# ROL2-C1-P01.net
KiCad netlist of a schematic drawn in Altium Designer
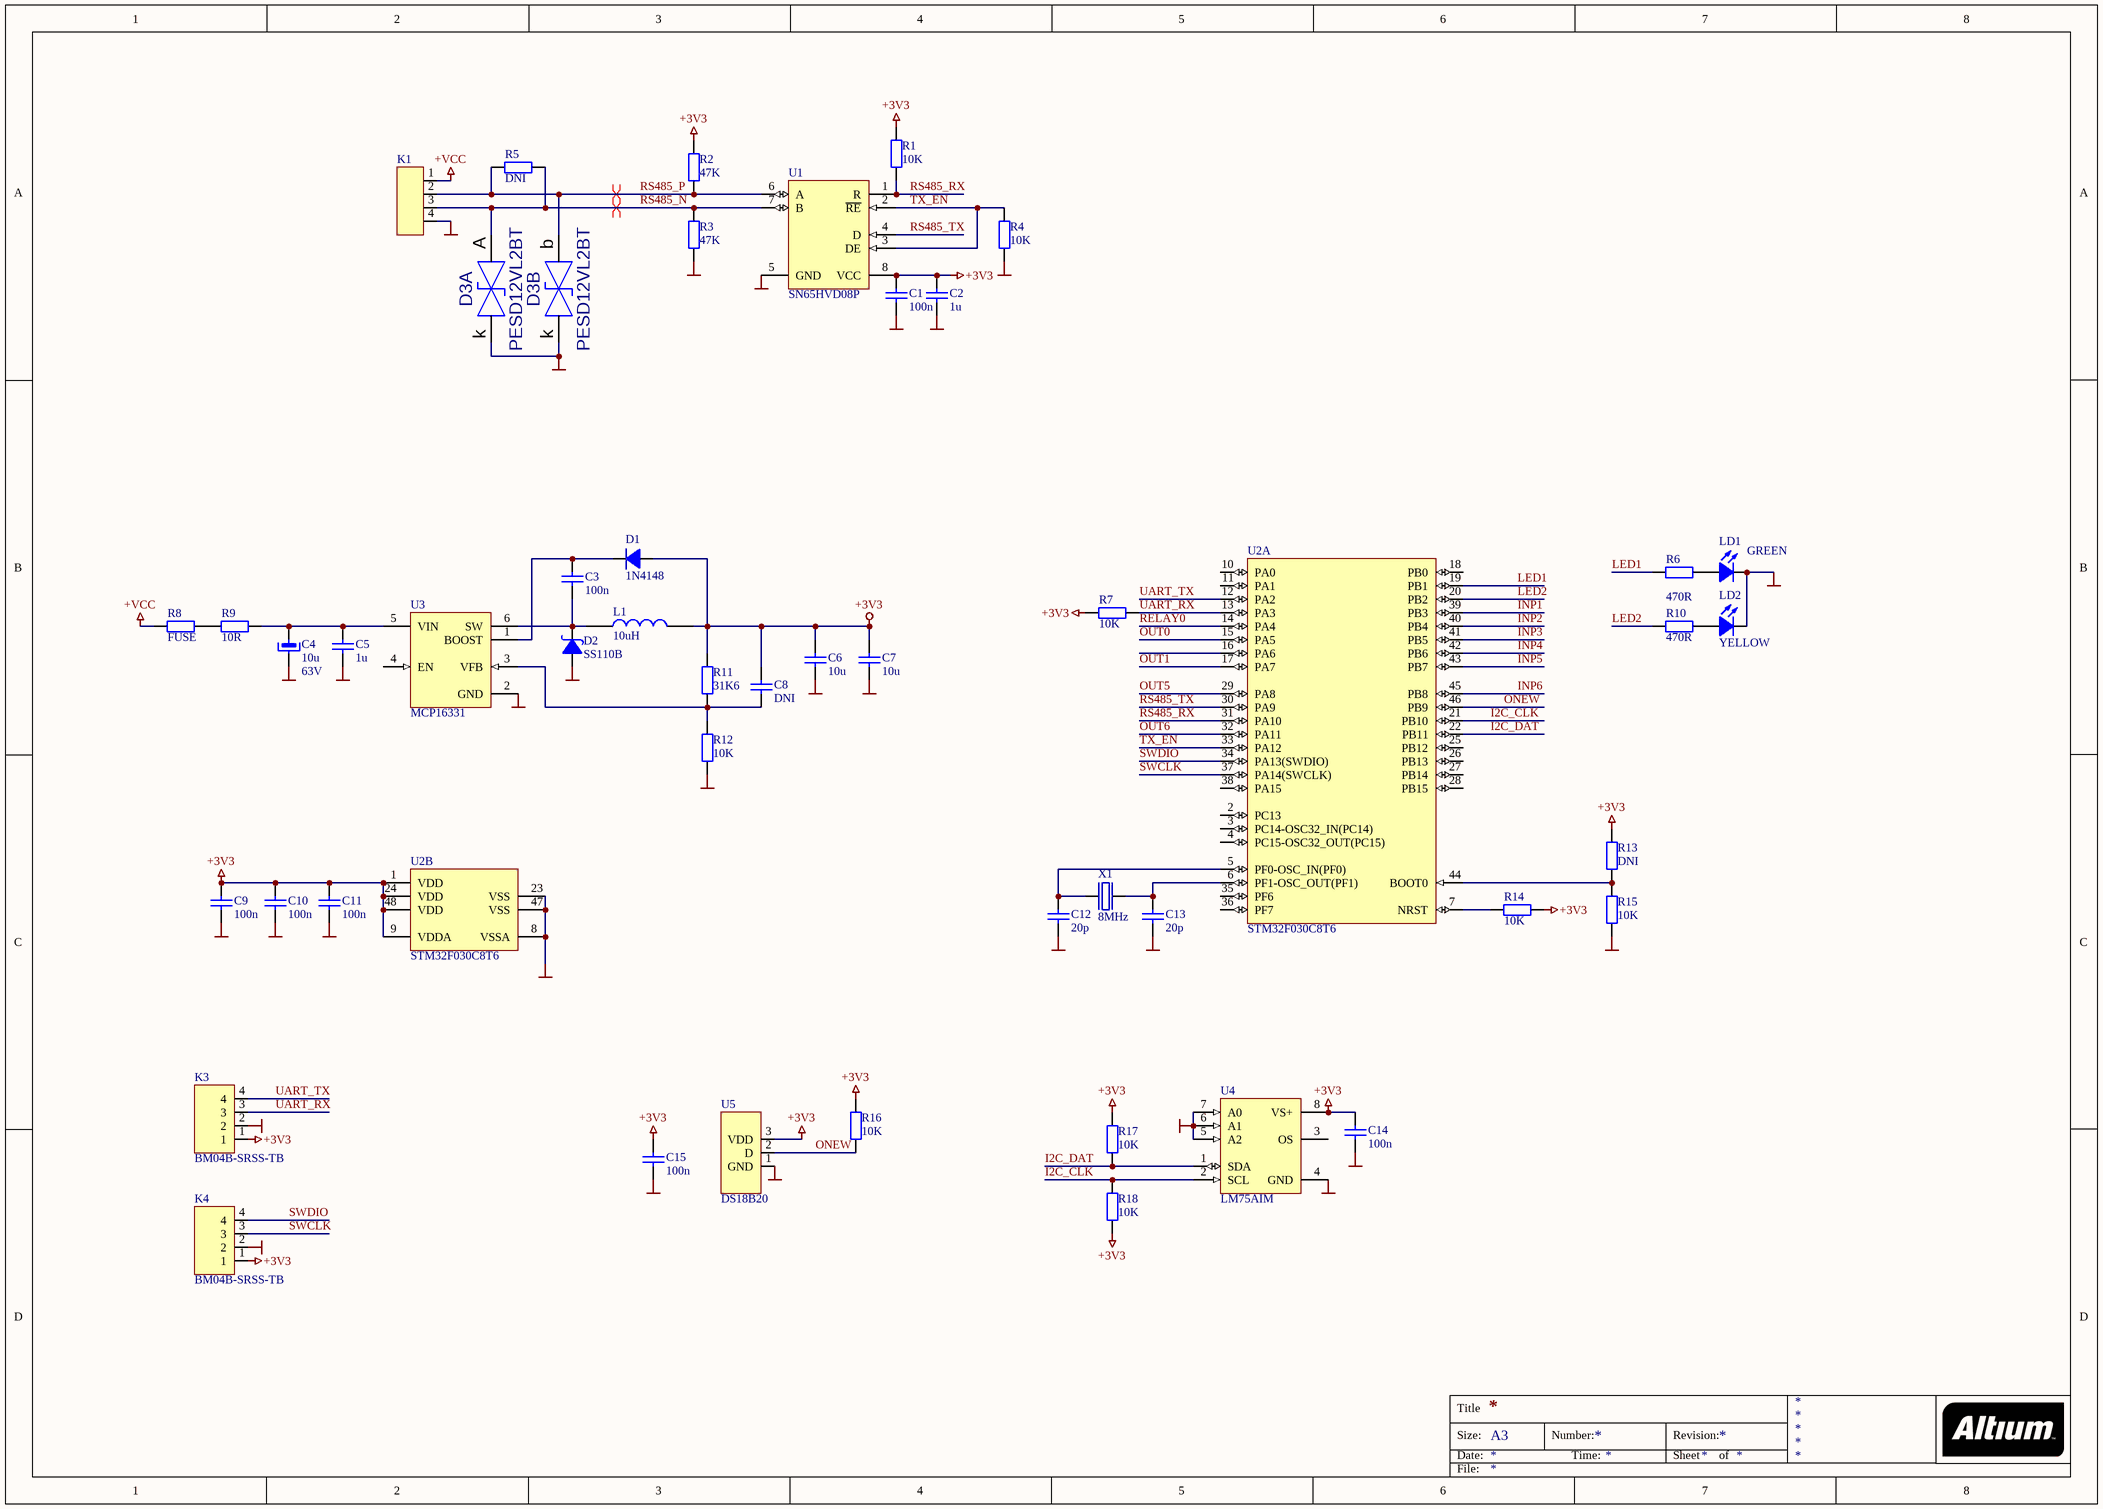
[diagram p0: ROL2-C1-P01.SchDoc]

(export (version "E")
  (design (tool "Eeschema 10.0.6"))
  (components
    (comp (ref "C1")
      (value "100n")
      (footprint "Passive:CC0805-1")
      (description "Capacitor chip ceramic 0805")
      (libsource (lib "CapChipCer") (part "CAPCC0805_1U50VX7R"))
    )
    (comp (ref "C2")
      (value "1u")
      (footprint "Passive:CC0805-1")
      (description "Capacitor chip ceramic 0805")
      (libsource (lib "CapChipCer") (part "CAPCC0805_1U50VX7R"))
    )
    (comp (ref "C3")
      (value "100n")
      (footprint "Passive:CC0805-1")
      (description "Capacitor chip ceramic 0805")
      (libsource (lib "CapChipCer") (part "CAPCC0805_1U50VX7R"))
    )
    (comp (ref "C4")
      (value "10u")
      (footprint "CAPPS-D6.3X7.7")
      (description "Capacitor electrolitic SMD 6.3X6.3X7.7MM low ESR")
      (fields (field (name "COMMENT2") "63V"))
      (libsource (lib "CapElectTht") (part "CAPPS100U25VFP"))
    )
    (comp (ref "C5")
      (value "1u")
      (footprint "Passive:CC1210-1")
      (description "Capacitor chip ceramic 1210")
      (libsource (lib "CapChipCer") (part "CAPCC1210_1U100VX7R"))
    )
    (comp (ref "C6")
      (value "10u")
      (footprint "CC0805-1")
      (description "Capacitor chip ceramic 0805")
      (libsource (lib "CapChipCer") (part "CAPCC0805_10U16VX5R"))
    )
    (comp (ref "C7")
      (value "10u")
      (footprint "CC0805-1")
      (description "Capacitor chip ceramic 0805")
      (libsource (lib "CapChipCer") (part "CAPCC0805_10U16VX5R"))
    )
    (comp (ref "C8")
      (value "DNI")
      (footprint "Passive:CC0805-1")
      (description "Capacitor chip ceramic 0805")
      (libsource (lib "CapChipCer") (part "CAPCC0805_1U50VX7R"))
    )
    (comp (ref "C9")
      (value "100n")
      (footprint "CC0805-1")
      (description "Capacitor chip ceramic 0805")
      (libsource (lib "CapChipCer") (part "CAPCC0805_100N50VX7R"))
    )
    (comp (ref "C10")
      (value "100n")
      (footprint "CC0805-1")
      (description "Capacitor chip ceramic 0805")
      (libsource (lib "CapChipCer") (part "CAPCC0805_100N50VX7R"))
    )
    (comp (ref "C11")
      (value "100n")
      (footprint "CC0805-1")
      (description "Capacitor chip ceramic 0805")
      (libsource (lib "CapChipCer") (part "CAPCC0805_100N50VX7R"))
    )
    (comp (ref "C12")
      (value "20p")
      (footprint "CC0805-1")
      (description "Capacitor chip ceramic 0805")
      (libsource (lib "CapChipCer") (part "CAPCC0805_100N50VX7R"))
    )
    (comp (ref "C13")
      (value "20p")
      (footprint "CC0805-1")
      (description "Capacitor chip ceramic 0805")
      (libsource (lib "CapChipCer") (part "CAPCC0805_100N50VX7R"))
    )
    (comp (ref "C14")
      (value "100n")
      (footprint "CC0805-1")
      (description "Capacitor chip ceramic 0805")
      (libsource (lib "CapChipCer") (part "CAPCC0805_100N50VX7R"))
    )
    (comp (ref "C15")
      (value "100n")
      (footprint "CC0805-1")
      (description "Capacitor chip ceramic 0805")
      (libsource (lib "CapChipCer") (part "CAPCC0805_100N50VX7R"))
    )
    (comp (ref "D1")
      (value "1N4148")
      (footprint "Active:SOD323")
      (description "Small Signal Diode")
      (fields (field (name "MANUFACTURER") "Vishay"))
      (libsource (lib "Discrete") (part "D-1N4148WS"))
    )
    (comp (ref "D2")
      (value "SS110B")
      (footprint "Passive:DO-214AC")
      (description "Schottky Diode")
      (fields (field (name "MANUFACTURER") "multicomp"))
      (libsource (lib "Discrete") (part "CD214A-B240LF-0.3V@1A"))
    )
    (comp (ref "D3")
      (value "PESD12VL2BT")
      (footprint "SOT-23_NUP2105L(Primary)")
      (description "Diode")
      (libsource (lib "fractal_lib") (part "NUP2105L"))
    )
    (comp (ref "K1")
      (value "Terminal Block Connector, 3.81mm, Right Angle")
      (footprint "CONN_3.81_4")
      (description "Terminal Block Connector, 3.81mm, 4pin")
      (libsource (lib "fractal_lib") (part "CONN_TB_3.81_4PIN"))
    )
    (comp (ref "K3")
      (value "BM04B-SRSS-TB")
      (footprint "JST-SH-4pin")
      (description "JST connector 4pin vertical")
      (libsource (lib "fractal_lib") (part "JST-SH-BM04B-SRSS-TB"))
    )
    (comp (ref "K4")
      (value "BM04B-SRSS-TB")
      (footprint "JST-SH-4pin")
      (description "JST connector 4pin vertical")
      (libsource (lib "fractal_lib") (part "JST-SH-BM04B-SRSS-TB"))
    )
    (comp (ref "L1")
      (value "10uH")
      (footprint "IND-LQH32CN4R7M33l")
      (description "Chip Inductor 4 x 4 mm")
      (fields (field (name "MANUFACTURER") "Murata"))
      (libsource (lib "Induct") (part "LQH44PN100MP0L"))
    )
    (comp (ref "LD1")
      (value "GREEN")
      (footprint "Active:LEDGREENC190")
      (description "LED green HSMG vertical")
      (fields (field (name "MANUFACTURER") "Avago"))
      (libsource (lib "Discrete") (part "LED-GREEN0603V"))
    )
    (comp (ref "LD2")
      (value "YELLOW")
      (footprint "Active:LEDYELLOWC190")
      (description "LED yellow HSMY vertical")
      (fields (field (name "MANUFACTURER") "Avago"))
      (libsource (lib "Discrete") (part "LED-YELLOW0603V"))
    )
    (comp (ref "R1")
      (value "10K")
      (footprint "RC0805-1")
      (description "Chip Resistor 0805")
      (libsource (lib "") (part "RES0805_1"))
    )
    (comp (ref "R2")
      (value "47K")
      (footprint "RC0805-1")
      (description "Chip Resistor 0805")
      (libsource (lib "Resistors") (part "RES0805"))
    )
    (comp (ref "R3")
      (value "47K")
      (footprint "RC0805-1")
      (description "Chip Resistor 0805")
      (libsource (lib "Resistors") (part "RES0805"))
    )
    (comp (ref "R4")
      (value "10K")
      (footprint "RC0805-1")
      (description "Chip Resistor 0805")
      (libsource (lib "") (part "RES0805_1"))
    )
    (comp (ref "R5")
      (value "DNI")
      (footprint "RC0805-1")
      (description "Chip Resistor 0805")
      (libsource (lib "") (part "RES0805_1"))
    )
    (comp (ref "R6")
      (value "470R")
      (footprint "RC0805-1")
      (description "Chip Resistor 0805")
      (libsource (lib "") (part "RES0805_1"))
    )
    (comp (ref "R7")
      (value "10K")
      (footprint "RC0805-1")
      (description "Chip Resistor 0805")
      (libsource (lib "") (part "RES0805_1"))
    )
    (comp (ref "R8")
      (value "FUSE")
      (footprint "RC1206-1")
      (description "Chip Resistor 1206")
      (libsource (lib "Resistors") (part "RES1206"))
    )
    (comp (ref "R9")
      (value "10R")
      (footprint "RC0805-1")
      (description "Chip Resistor 0805")
      (libsource (lib "") (part "RES0805_3"))
    )
    (comp (ref "R10")
      (value "470R")
      (footprint "RC0805-1")
      (description "Chip Resistor 0805")
      (libsource (lib "") (part "RES0805_1"))
    )
    (comp (ref "R11")
      (value "31K6")
      (footprint "RC0805-1")
      (description "Chip Resistor 0805")
      (libsource (lib "Resistors") (part "RES0805"))
    )
    (comp (ref "R12")
      (value "10K")
      (footprint "RC0805-1")
      (description "Chip Resistor 0805")
      (libsource (lib "Resistors") (part "RES0805"))
    )
    (comp (ref "R13")
      (value "DNI")
      (footprint "RC0805-1")
      (description "Chip Resistor 0805")
      (libsource (lib "Resistors") (part "RES0805"))
    )
    (comp (ref "R14")
      (value "10K")
      (footprint "RC0805-1")
      (description "Chip Resistor 0805")
      (libsource (lib "") (part "RES0805_3"))
    )
    (comp (ref "R15")
      (value "10K")
      (footprint "RC0805-1")
      (description "Chip Resistor 0805")
      (libsource (lib "") (part "RES0805_2"))
    )
    (comp (ref "R16")
      (value "10K")
      (footprint "RC0805-1")
      (description "Chip Resistor 0805")
      (libsource (lib "") (part "RES0805_2"))
    )
    (comp (ref "R17")
      (value "10K")
      (footprint "RC0805-1")
      (description "Chip Resistor 0805")
      (libsource (lib "") (part "RES0805_2"))
    )
    (comp (ref "R18")
      (value "10K")
      (footprint "RC0805-1")
      (description "Chip Resistor 0805")
      (libsource (lib "Resistors") (part "RES0805"))
    )
    (comp (ref "U1")
      (value "SN65HVD08P")
      (footprint "M08A_M")
      (description "3.3 / 5 V RS-485 Transceiver, 10 Mbps, Half Duplex, -40 to 85 degC, 8-pin PDIP (P), Pb-Free (RoHS)")
      (fields (field (name "MANUFACTURER") "Texas Instruments"))
      (libsource (lib "fractal_lib") (part "SN65HVD08P"))
    )
    (comp (ref "U2")
      (value "STM32F030C8T6")
      (footprint "STM-LQFP48_N")
      (libsource (lib "fractal_lib") (part "STM32F030C8T6"))
    )
    (comp (ref "U3")
      (value "MCP16331")
      (footprint "MCHP-SOT-23-CH6_N")
      (fields (field (name "MANUFACTURER") "Microchip") (field (name "PARTNUMBER") "MCP16301T-E/CH"))
      (libsource (lib "fractal_lib") (part "MCP16301T-E/CH"))
    )
    (comp (ref "U4")
      (value "LM75AIM")
      (footprint "M08A_N")
      (description "Digital Temperature Sensor and Thermal Watchdog with Two-Wire Interface, 8-pin Narrow SOIC")
      (fields (field (name "MANUFACTURER") "National Semiconductor"))
      (libsource (lib "fractal_lib") (part "LM75AIM"))
    )
    (comp (ref "U5")
      (value "DS18B20")
      (footprint "TO92")
      (description "digital temperature sensor")
      (libsource (lib "fractal_lib") (part "DS18B20"))
    )
    (comp (ref "X1")
      (value "8MHz")
      (footprint "OSCCC150X320X9-2N_big")
      (description "SMD Crystal 8MHz")
      (libsource (lib "fractal_lib") (part "XTAL-SMD_8MHz"))
    )
  )
  (nets
    (net (code "1") (name "+3V3") (class "Default")
      (node (ref "C1") (pin "2") (pinfunction "2_2") (pintype "passive"))
      (node (ref "C10") (pin "2") (pinfunction "2_2") (pintype "passive"))
      (node (ref "C11") (pin "2") (pinfunction "2_2") (pintype "passive"))
      (node (ref "C14") (pin "2") (pinfunction "2_2") (pintype "passive"))
      (node (ref "C15") (pin "2") (pinfunction "2_2") (pintype "passive"))
      (node (ref "C2") (pin "2") (pinfunction "2_2") (pintype "passive"))
      (node (ref "C6") (pin "2") (pinfunction "2_2") (pintype "passive"))
      (node (ref "C7") (pin "2") (pinfunction "2_2") (pintype "passive"))
      (node (ref "C8") (pin "2") (pinfunction "2_2") (pintype "passive"))
      (node (ref "C9") (pin "2") (pinfunction "2_2") (pintype "passive"))
      (node (ref "D1") (pin "2") (pinfunction "A_2") (pintype "passive"))
      (node (ref "K3") (pin "1") (pinfunction "1_1") (pintype "passive"))
      (node (ref "K4") (pin "1") (pinfunction "1_1") (pintype "passive"))
      (node (ref "L1") (pin "2") (pinfunction "2_2") (pintype "passive"))
      (node (ref "R1") (pin "2") (pinfunction "2_2") (pintype "passive"))
      (node (ref "R11") (pin "2") (pinfunction "2_2") (pintype "passive"))
      (node (ref "R13") (pin "2") (pinfunction "2_2") (pintype "passive"))
      (node (ref "R14") (pin "1") (pinfunction "1_1") (pintype "passive"))
      (node (ref "R16") (pin "1") (pinfunction "1_1") (pintype "passive"))
      (node (ref "R17") (pin "1") (pinfunction "1_1") (pintype "passive"))
      (node (ref "R18") (pin "1") (pinfunction "1_1") (pintype "passive"))
      (node (ref "R2") (pin "2") (pinfunction "2_2") (pintype "passive"))
      (node (ref "R7") (pin "1") (pinfunction "1_1") (pintype "passive"))
      (node (ref "U1") (pin "8") (pinfunction "VCC_8") (pintype "power_in"))
      (node (ref "U2") (pin "1") (pinfunction "VDD_1") (pintype "power_in"))
      (node (ref "U2") (pin "24") (pinfunction "VDD_24") (pintype "power_in"))
      (node (ref "U2") (pin "48") (pinfunction "VDD_48") (pintype "power_in"))
      (node (ref "U2") (pin "9") (pinfunction "VDDA_9") (pintype "power_in"))
      (node (ref "U4") (pin "8") (pinfunction "VS+_8") (pintype "power_in"))
      (node (ref "U5") (pin "3") (pinfunction "VDD_3") (pintype "passive"))
    )
    (net (code "2") (name "+VCC") (class "Default")
      (node (ref "K1") (pin "1") (pinfunction "A_1") (pintype "passive"))
      (node (ref "R8") (pin "1") (pinfunction "1_1") (pintype "passive"))
    )
    (net (code "3") (name "/I2C_CLK") (class "Default")
      (node (ref "R18") (pin "2") (pinfunction "2_2") (pintype "passive"))
      (node (ref "U2") (pin "21") (pinfunction "PB10_21") (pintype "bidirectional"))
      (node (ref "U4") (pin "2") (pinfunction "SCL_2") (pintype "input"))
    )
    (net (code "4") (name "/I2C_DAT") (class "Default")
      (node (ref "R17") (pin "2") (pinfunction "2_2") (pintype "passive"))
      (node (ref "U2") (pin "22") (pinfunction "PB11_22") (pintype "bidirectional"))
      (node (ref "U4") (pin "1") (pinfunction "SDA_1") (pintype "bidirectional"))
    )
    (net (code "5") (name "/INP1") (class "Default")
      (node (ref "U2") (pin "39") (pinfunction "PB3_39") (pintype "bidirectional"))
    )
    (net (code "6") (name "/INP2") (class "Default")
      (node (ref "U2") (pin "40") (pinfunction "PB4_40") (pintype "bidirectional"))
    )
    (net (code "7") (name "/INP3") (class "Default")
      (node (ref "U2") (pin "41") (pinfunction "PB5_41") (pintype "bidirectional"))
    )
    (net (code "8") (name "/INP4") (class "Default")
      (node (ref "U2") (pin "42") (pinfunction "PB6_42") (pintype "bidirectional"))
    )
    (net (code "9") (name "/INP5") (class "Default")
      (node (ref "U2") (pin "43") (pinfunction "PB7_43") (pintype "bidirectional"))
    )
    (net (code "10") (name "/INP6") (class "Default")
      (node (ref "U2") (pin "45") (pinfunction "PB8_45") (pintype "bidirectional"))
    )
    (net (code "11") (name "/LED1") (class "Default")
      (node (ref "R6") (pin "1") (pinfunction "1_1") (pintype "passive"))
      (node (ref "U2") (pin "19") (pinfunction "PB1_19") (pintype "bidirectional"))
    )
    (net (code "12") (name "/LED2") (class "Default")
      (node (ref "R10") (pin "1") (pinfunction "1_1") (pintype "passive"))
      (node (ref "U2") (pin "20") (pinfunction "PB2_20") (pintype "bidirectional"))
    )
    (net (code "13") (name "/ONEW") (class "Default")
      (node (ref "R16") (pin "2") (pinfunction "2_2") (pintype "passive"))
      (node (ref "U2") (pin "46") (pinfunction "PB9_46") (pintype "bidirectional"))
      (node (ref "U5") (pin "2") (pinfunction "D_2") (pintype "passive"))
    )
    (net (code "14") (name "/OUT0") (class "Default")
      (node (ref "U2") (pin "15") (pinfunction "PA5_15") (pintype "bidirectional"))
    )
    (net (code "15") (name "/OUT1") (class "Default")
      (node (ref "U2") (pin "17") (pinfunction "PA7_17") (pintype "bidirectional"))
    )
    (net (code "16") (name "/OUT5") (class "Default")
      (node (ref "U2") (pin "29") (pinfunction "PA8_29") (pintype "bidirectional"))
    )
    (net (code "17") (name "/OUT6") (class "Default")
      (node (ref "U2") (pin "32") (pinfunction "PA11_32") (pintype "bidirectional"))
    )
    (net (code "18") (name "/RELAY0") (class "Default")
      (node (ref "U2") (pin "14") (pinfunction "PA4_14") (pintype "bidirectional"))
    )
    (net (code "19") (name "/RS485_N") (class "Default")
      (node (ref "D3") (pin "A") (pinfunction "A_A") (pintype "passive"))
      (node (ref "K1") (pin "3") (pinfunction "A_3") (pintype "passive"))
      (node (ref "R3") (pin "2") (pinfunction "2_2") (pintype "passive"))
      (node (ref "R5") (pin "2") (pinfunction "2_2") (pintype "passive"))
      (node (ref "U1") (pin "7") (pinfunction "B_7") (pintype "bidirectional"))
    )
    (net (code "20") (name "/RS485_P") (class "Default")
      (node (ref "D3") (pin "b") (pinfunction "A_b") (pintype "passive"))
      (node (ref "K1") (pin "2") (pinfunction "K_2") (pintype "passive"))
      (node (ref "R2") (pin "1") (pinfunction "1_1") (pintype "passive"))
      (node (ref "R5") (pin "1") (pinfunction "1_1") (pintype "passive"))
      (node (ref "U1") (pin "6") (pinfunction "A_6") (pintype "bidirectional"))
    )
    (net (code "21") (name "/RS485_RX") (class "Default")
      (node (ref "R1") (pin "1") (pinfunction "1_1") (pintype "passive"))
      (node (ref "U1") (pin "1") (pinfunction "R_1") (pintype "tri_state"))
      (node (ref "U2") (pin "31") (pinfunction "PA10_31") (pintype "bidirectional"))
    )
    (net (code "22") (name "/RS485_TX") (class "Default")
      (node (ref "U1") (pin "4") (pinfunction "D_4") (pintype "input"))
      (node (ref "U2") (pin "30") (pinfunction "PA9_30") (pintype "bidirectional"))
    )
    (net (code "23") (name "/SWCLK") (class "Default")
      (node (ref "K4") (pin "3") (pinfunction "3_3") (pintype "passive"))
      (node (ref "U2") (pin "37") (pinfunction "PA14(SWCLK)_37") (pintype "bidirectional"))
    )
    (net (code "24") (name "/SWDIO") (class "Default")
      (node (ref "K4") (pin "4") (pinfunction "4_4") (pintype "passive"))
      (node (ref "U2") (pin "34") (pinfunction "PA13(SWDIO)_34") (pintype "bidirectional"))
    )
    (net (code "25") (name "/TX_EN") (class "Default")
      (node (ref "R4") (pin "2") (pinfunction "2_2") (pintype "passive"))
      (node (ref "U1") (pin "2") (pinfunction "~{RE}_2") (pintype "input"))
      (node (ref "U1") (pin "3") (pinfunction "DE_3") (pintype "input"))
      (node (ref "U2") (pin "33") (pinfunction "PA12_33") (pintype "bidirectional"))
    )
    (net (code "26") (name "/UART_RX") (class "Default")
      (node (ref "K3") (pin "3") (pinfunction "3_3") (pintype "passive"))
      (node (ref "R7") (pin "2") (pinfunction "2_2") (pintype "passive"))
      (node (ref "U2") (pin "13") (pinfunction "PA3_13") (pintype "bidirectional"))
    )
    (net (code "27") (name "/UART_TX") (class "Default")
      (node (ref "K3") (pin "4") (pinfunction "4_4") (pintype "passive"))
      (node (ref "U2") (pin "12") (pinfunction "PA2_12") (pintype "bidirectional"))
    )
    (net (code "28") (name "GND") (class "Default")
      (node (ref "C1") (pin "1") (pinfunction "1_1") (pintype "passive"))
      (node (ref "C10") (pin "1") (pinfunction "1_1") (pintype "passive"))
      (node (ref "C11") (pin "1") (pinfunction "1_1") (pintype "passive"))
      (node (ref "C12") (pin "1") (pinfunction "1_1") (pintype "passive"))
      (node (ref "C13") (pin "1") (pinfunction "1_1") (pintype "passive"))
      (node (ref "C14") (pin "1") (pinfunction "1_1") (pintype "passive"))
      (node (ref "C15") (pin "1") (pinfunction "1_1") (pintype "passive"))
      (node (ref "C2") (pin "1") (pinfunction "1_1") (pintype "passive"))
      (node (ref "C4") (pin "2") (pinfunction "2_2") (pintype "passive"))
      (node (ref "C5") (pin "1") (pinfunction "1_1") (pintype "passive"))
      (node (ref "C6") (pin "1") (pinfunction "1_1") (pintype "passive"))
      (node (ref "C7") (pin "1") (pinfunction "1_1") (pintype "passive"))
      (node (ref "C9") (pin "1") (pinfunction "1_1") (pintype "passive"))
      (node (ref "D2") (pin "A") (pinfunction "A_A") (pintype "passive"))
      (node (ref "D3") (pin "k") (pinfunction "K_k") (pintype "power_in"))
      (node (ref "K1") (pin "4") (pinfunction "K_4") (pintype "passive"))
      (node (ref "K3") (pin "2") (pinfunction "2_2") (pintype "passive"))
      (node (ref "K4") (pin "2") (pinfunction "2_2") (pintype "passive"))
      (node (ref "LD1") (pin "1") (pinfunction "C_1") (pintype "passive"))
      (node (ref "LD2") (pin "1") (pinfunction "C_1") (pintype "passive"))
      (node (ref "R12") (pin "1") (pinfunction "1_1") (pintype "passive"))
      (node (ref "R15") (pin "2") (pinfunction "2_2") (pintype "passive"))
      (node (ref "R3") (pin "1") (pinfunction "1_1") (pintype "passive"))
      (node (ref "R4") (pin "1") (pinfunction "1_1") (pintype "passive"))
      (node (ref "U1") (pin "5") (pinfunction "GND_5") (pintype "power_in"))
      (node (ref "U2") (pin "23") (pinfunction "VSS_23") (pintype "power_in"))
      (node (ref "U2") (pin "47") (pinfunction "VSS_47") (pintype "power_in"))
      (node (ref "U2") (pin "8") (pinfunction "VSSA_8") (pintype "power_in"))
      (node (ref "U3") (pin "2") (pinfunction "GND_2") (pintype "power_in"))
      (node (ref "U4") (pin "4") (pinfunction "GND_4") (pintype "power_in"))
      (node (ref "U4") (pin "5") (pinfunction "A2_5") (pintype "input"))
      (node (ref "U4") (pin "6") (pinfunction "A1_6") (pintype "input"))
      (node (ref "U4") (pin "7") (pinfunction "A0_7") (pintype "input"))
      (node (ref "U5") (pin "1") (pinfunction "GND_1") (pintype "passive"))
    )
    (net (code "29") (name "Net-(D1-C)") (class "Default")
      (node (ref "C3") (pin "2") (pinfunction "2_2") (pintype "passive"))
      (node (ref "D1") (pin "1") (pinfunction "C_1") (pintype "passive"))
      (node (ref "U3") (pin "1") (pinfunction "BOOST_1") (pintype "power_in"))
    )
    (net (code "30") (name "Net-(LD1-A)") (class "Default")
      (node (ref "LD1") (pin "2") (pinfunction "A_2") (pintype "passive"))
      (node (ref "R6") (pin "2") (pinfunction "2_2") (pintype "passive"))
    )
    (net (code "31") (name "Net-(LD2-A)") (class "Default")
      (node (ref "LD2") (pin "2") (pinfunction "A_2") (pintype "passive"))
      (node (ref "R10") (pin "2") (pinfunction "2_2") (pintype "passive"))
    )
    (net (code "32") (name "Net-(R8-Pad2)") (class "Default")
      (node (ref "R8") (pin "2") (pinfunction "2_2") (pintype "passive"))
      (node (ref "R9") (pin "2") (pinfunction "2_2") (pintype "passive"))
    )
    (net (code "33") (name "Net-(U2A-BOOT0)") (class "Default")
      (node (ref "R13") (pin "1") (pinfunction "1_1") (pintype "passive"))
      (node (ref "R15") (pin "1") (pinfunction "1_1") (pintype "passive"))
      (node (ref "U2") (pin "44") (pinfunction "BOOT0_44") (pintype "input"))
    )
    (net (code "34") (name "Net-(U2A-NRST)") (class "Default")
      (node (ref "R14") (pin "2") (pinfunction "2_2") (pintype "passive"))
      (node (ref "U2") (pin "7") (pinfunction "NRST_7") (pintype "bidirectional"))
    )
    (net (code "35") (name "Net-(U2A-PF0-OSC_IN(PF0))") (class "Default")
      (node (ref "C12") (pin "2") (pinfunction "2_2") (pintype "passive"))
      (node (ref "U2") (pin "5") (pinfunction "PF0-OSC_IN(PF0)_5") (pintype "bidirectional"))
      (node (ref "X1") (pin "1") (pinfunction "OUT_1") (pintype "power_in"))
    )
    (net (code "36") (name "Net-(U2A-PF1-OSC_OUT(PF1))") (class "Default")
      (node (ref "C13") (pin "2") (pinfunction "2_2") (pintype "passive"))
      (node (ref "U2") (pin "6") (pinfunction "PF1-OSC_OUT(PF1)_6") (pintype "bidirectional"))
      (node (ref "X1") (pin "2") (pinfunction "IN_2") (pintype "passive"))
    )
    (net (code "37") (name "Net-(U3-SW)") (class "Default")
      (node (ref "C3") (pin "1") (pinfunction "1_1") (pintype "passive"))
      (node (ref "D2") (pin "K") (pinfunction "K_K") (pintype "passive"))
      (node (ref "L1") (pin "1") (pinfunction "1_1") (pintype "passive"))
      (node (ref "U3") (pin "6") (pinfunction "SW_6") (pintype "power_in"))
    )
    (net (code "38") (name "Net-(U3-VFB)") (class "Default")
      (node (ref "C8") (pin "1") (pinfunction "1_1") (pintype "passive"))
      (node (ref "R11") (pin "1") (pinfunction "1_1") (pintype "passive"))
      (node (ref "R12") (pin "2") (pinfunction "2_2") (pintype "passive"))
      (node (ref "U3") (pin "3") (pinfunction "VFB_3") (pintype "input"))
    )
    (net (code "39") (name "Net-(U3-VIN)") (class "Default")
      (node (ref "C4") (pin "1") (pinfunction "1_1") (pintype "passive"))
      (node (ref "C5") (pin "2") (pinfunction "2_2") (pintype "passive"))
      (node (ref "R9") (pin "1") (pinfunction "1_1") (pintype "passive"))
      (node (ref "U3") (pin "5") (pinfunction "VIN_5") (pintype "power_in"))
    )
    (net (code "40") (name "unconnected-(U2A-PA0-Pad10)") (class "Default")
      (node (ref "U2") (pin "10") (pinfunction "PA0_10") (pintype "bidirectional"))
    )
    (net (code "41") (name "unconnected-(U2A-PA1-Pad11)") (class "Default")
      (node (ref "U2") (pin "11") (pinfunction "PA1_11") (pintype "bidirectional"))
    )
    (net (code "42") (name "unconnected-(U2A-PA6-Pad16)") (class "Default")
      (node (ref "U2") (pin "16") (pinfunction "PA6_16") (pintype "bidirectional"))
    )
    (net (code "43") (name "unconnected-(U2A-PA15-Pad38)") (class "Default")
      (node (ref "U2") (pin "38") (pinfunction "PA15_38") (pintype "bidirectional"))
    )
    (net (code "44") (name "unconnected-(U2A-PB0-Pad18)") (class "Default")
      (node (ref "U2") (pin "18") (pinfunction "PB0_18") (pintype "bidirectional"))
    )
    (net (code "45") (name "unconnected-(U2A-PB12-Pad25)") (class "Default")
      (node (ref "U2") (pin "25") (pinfunction "PB12_25") (pintype "bidirectional"))
    )
    (net (code "46") (name "unconnected-(U2A-PB13-Pad26)") (class "Default")
      (node (ref "U2") (pin "26") (pinfunction "PB13_26") (pintype "bidirectional"))
    )
    (net (code "47") (name "unconnected-(U2A-PB14-Pad27)") (class "Default")
      (node (ref "U2") (pin "27") (pinfunction "PB14_27") (pintype "bidirectional"))
    )
    (net (code "48") (name "unconnected-(U2A-PB15-Pad28)") (class "Default")
      (node (ref "U2") (pin "28") (pinfunction "PB15_28") (pintype "bidirectional"))
    )
    (net (code "49") (name "unconnected-(U2A-PC13-Pad2)") (class "Default")
      (node (ref "U2") (pin "2") (pinfunction "PC13_2") (pintype "bidirectional"))
    )
    (net (code "50") (name "unconnected-(U2A-PC14-OSC32_IN(PC14)-Pad3)") (class "Default")
      (node (ref "U2") (pin "3") (pinfunction "PC14-OSC32_IN(PC14)_3") (pintype "bidirectional"))
    )
    (net (code "51") (name "unconnected-(U2A-PC15-OSC32_OUT(PC15)-Pad4)") (class "Default")
      (node (ref "U2") (pin "4") (pinfunction "PC15-OSC32_OUT(PC15)_4") (pintype "bidirectional"))
    )
    (net (code "52") (name "unconnected-(U2A-PF6-Pad35)") (class "Default")
      (node (ref "U2") (pin "35") (pinfunction "PF6_35") (pintype "bidirectional"))
    )
    (net (code "53") (name "unconnected-(U2A-PF7-Pad36)") (class "Default")
      (node (ref "U2") (pin "36") (pinfunction "PF7_36") (pintype "bidirectional"))
    )
    (net (code "54") (name "unconnected-(U3-EN-Pad4)") (class "Default")
      (node (ref "U3") (pin "4") (pinfunction "EN_4") (pintype "input"))
    )
    (net (code "55") (name "unconnected-(U4-OS-Pad3)") (class "Default")
      (node (ref "U4") (pin "3") (pinfunction "OS_3") (pintype "open_collector"))
    )
  )
)
